# accero_humid_rtc.net
KiCad netlist of a schematic drawn in Altium Designer
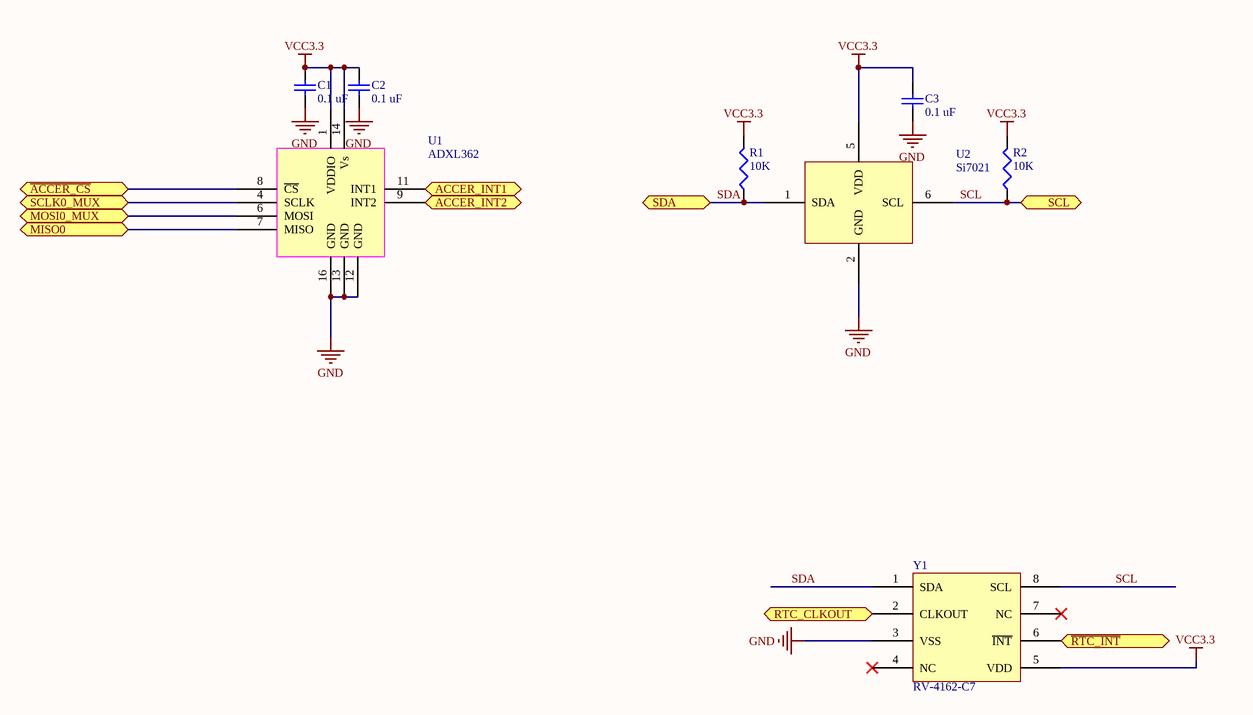
[diagram p0: accero_humid_rtc.SchDoc]

(export (version "E")
  (design (tool "Eeschema 10.0.6"))
  (components
    (comp (ref "C1")
      (value "0.1 uF")
      (footprint "0402")
      (description "Ceramic capacitor, 0.1u, 0402 package")
      (fields (field (name "TOLERANCE") "10%") (field (name "Comment") "Ceramic capacitor"))
      (libsource (lib "rlc") (part "C_0.1u_0402_ceramic"))
    )
    (comp (ref "C2")
      (value "0.1 uF")
      (footprint "0402")
      (description "Ceramic capacitor, 0.1u, 0402 package")
      (fields (field (name "TOLERANCE") "10%") (field (name "Comment") "Ceramic capacitor"))
      (libsource (lib "rlc") (part "C_0.1u_0402_ceramic"))
    )
    (comp (ref "C3")
      (value "0.1 uF")
      (footprint "0402")
      (description "Ceramic capacitor, 0.1u, 0402 package")
      (fields (field (name "TOLERANCE") "10%") (field (name "Comment") "Ceramic capacitor"))
      (libsource (lib "rlc") (part "C_0.1u_0402_ceramic"))
    )
    (comp (ref "R1")
      (value "10K")
      (footprint "0402")
      (description "Chip resistor, 10K, 0402 package")
      (fields (field (name "TOLERANCE") "1%") (field (name "POWER") "1/16 W"))
      (libsource (lib "rlc") (part "R_10K_0402"))
    )
    (comp (ref "R2")
      (value "10K")
      (footprint "0402")
      (description "Chip resistor, 10K, 0402 package")
      (fields (field (name "TOLERANCE") "1%") (field (name "POWER") "1/16 W"))
      (libsource (lib "rlc") (part "R_10K_0402"))
    )
    (comp (ref "U1")
      (value "ADXL362")
      (footprint "LGA_CC-16-4")
      (description "Micropower, 3-Axis, ±2 g/±4 g/±8 g  Digital Output MEMS Accelerometer")
      (libsource (lib "opo") (part "ADXL362"))
    )
    (comp (ref "U2")
      (value "Si7021")
      (footprint "opo:DFN6-Si7021")
      (description "Temperature and Humidity Sensor")
      (libsource (lib "opo") (part "Si7021"))
    )
    (comp (ref "Y1")
      (value "RV-4162-C7")
      (footprint "RV4162")
      (description "Real Time Clock Module with I2C Bus")
      (libsource (lib "opo") (part "RV-4162-C7"))
    )
  )
  (nets
    (net (code "1") (name "/ACCER_INT1") (class "Default")
      (node (ref "U1") (pin "11") (pinfunction "INT1_11") (pintype "passive"))
    )
    (net (code "2") (name "/ACCER_INT2") (class "Default")
      (node (ref "U1") (pin "9") (pinfunction "INT2_9") (pintype "passive"))
    )
    (net (code "3") (name "/MISO0") (class "Default")
      (node (ref "U1") (pin "7") (pinfunction "MISO_7") (pintype "passive"))
    )
    (net (code "4") (name "/MOSI0_MUX") (class "Default")
      (node (ref "U1") (pin "6") (pinfunction "MOSI_6") (pintype "passive"))
    )
    (net (code "5") (name "/RTC_CLKOUT") (class "Default")
      (node (ref "Y1") (pin "2") (pinfunction "CLKOUT_2") (pintype "passive"))
    )
    (net (code "6") (name "/SCL") (class "Default")
      (node (ref "R2") (pin "2") (pintype "passive"))
      (node (ref "U2") (pin "6") (pinfunction "SCL_6") (pintype "passive"))
      (node (ref "Y1") (pin "8") (pinfunction "SCL_8") (pintype "passive"))
    )
    (net (code "7") (name "/SCLK0_MUX") (class "Default")
      (node (ref "U1") (pin "4") (pinfunction "SCLK_4") (pintype "passive"))
    )
    (net (code "8") (name "/SDA") (class "Default")
      (node (ref "R1") (pin "2") (pintype "passive"))
      (node (ref "U2") (pin "1") (pinfunction "SDA_1") (pintype "passive"))
      (node (ref "Y1") (pin "1") (pinfunction "SDA_1") (pintype "passive"))
    )
    (net (code "9") (name "/~{ACCER_CS}") (class "Default")
      (node (ref "U1") (pin "8") (pinfunction "~{CS}_8") (pintype "passive"))
    )
    (net (code "10") (name "/~{RTC_INT}") (class "Default")
      (node (ref "Y1") (pin "6") (pinfunction "~{INT}_6") (pintype "passive"))
    )
    (net (code "11") (name "GND") (class "Default")
      (node (ref "C1") (pin "2") (pintype "passive"))
      (node (ref "C2") (pin "2") (pintype "passive"))
      (node (ref "C3") (pin "2") (pintype "passive"))
      (node (ref "U1") (pin "12") (pinfunction "GND_12") (pintype "passive"))
      (node (ref "U1") (pin "13") (pinfunction "GND_13") (pintype "passive"))
      (node (ref "U1") (pin "16") (pinfunction "GND_16") (pintype "passive"))
      (node (ref "U2") (pin "2") (pinfunction "GND_2") (pintype "passive"))
      (node (ref "Y1") (pin "3") (pinfunction "VSS_3") (pintype "passive"))
    )
    (net (code "12") (name "VCC3.3") (class "Default")
      (node (ref "C1") (pin "1") (pintype "passive"))
      (node (ref "C2") (pin "1") (pintype "passive"))
      (node (ref "C3") (pin "1") (pintype "passive"))
      (node (ref "R1") (pin "1") (pintype "passive"))
      (node (ref "R2") (pin "1") (pintype "passive"))
      (node (ref "U1") (pin "1") (pinfunction "VDDIO_1") (pintype "passive"))
      (node (ref "U1") (pin "14") (pinfunction "Vs_14") (pintype "passive"))
      (node (ref "U2") (pin "5") (pinfunction "VDD_5") (pintype "passive"))
      (node (ref "Y1") (pin "5") (pinfunction "VDD_5") (pintype "passive"))
    )
    (net (code "13") (name "unconnected-(U2-DNC-Pad3)") (class "Default")
      (node (ref "U2") (pin "3") (pinfunction "DNC_3") (pintype "passive"))
    )
    (net (code "14") (name "unconnected-(U2-DNC-Pad4)") (class "Default")
      (node (ref "U2") (pin "4") (pinfunction "DNC_4") (pintype "passive"))
    )
    (net (code "15") (name "unconnected-(U2-DNC-Pad7)") (class "Default")
      (node (ref "U2") (pin "7") (pinfunction "DNC_7") (pintype "passive"))
    )
    (net (code "16") (name "unconnected-(Y1-NC-Pad4)") (class "Default")
      (node (ref "Y1") (pin "4") (pinfunction "NC_4") (pintype "passive+no_connect"))
    )
    (net (code "17") (name "unconnected-(Y1-NC-Pad7)") (class "Default")
      (node (ref "Y1") (pin "7") (pinfunction "NC_7") (pintype "passive+no_connect"))
    )
  )
)
